# LEO_COTS_no_mult_tripler_rev1.net
KiCad netlist of a schematic drawn in Altium Designer
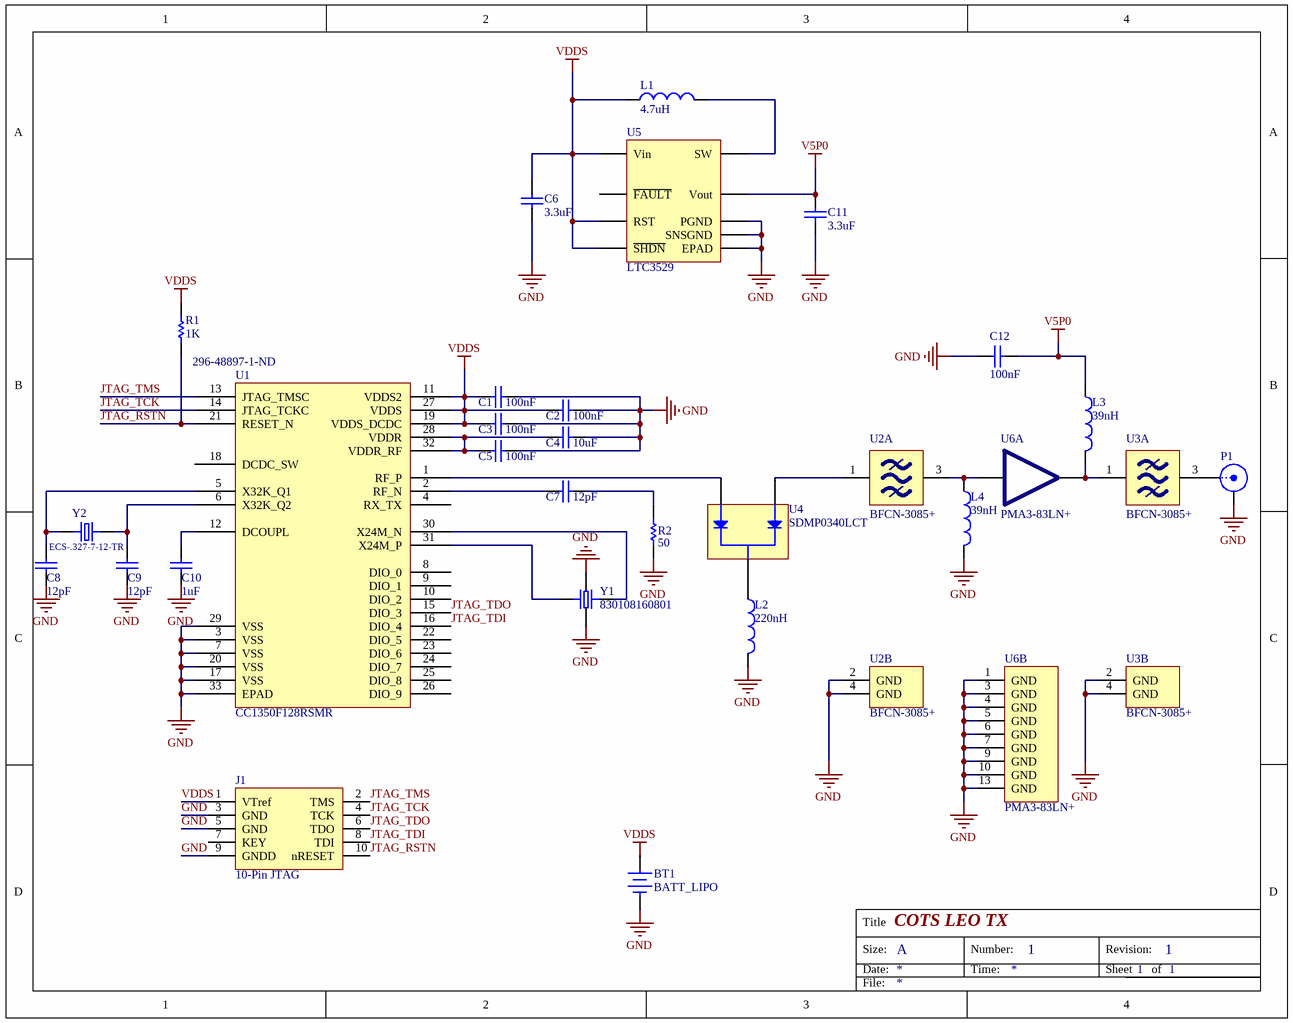
[diagram p0: LEO_COTS_no_mult_tripler_rev1.SchDoc]

(export (version "E")
  (design (tool "Eeschema 10.0.6"))
  (components
    (comp (ref "BT1")
      (value "BATT_LIPO")
      (footprint "LIPO_1cm_1cm")
      (libsource (lib "LEO_COTS_components") (part "BATT_LIPO"))
    )
    (comp (ref "C1")
      (value "100nF")
      (footprint "CAPC0603X04N")
      (description "CAP CER 100nF 0201")
      (fields (field (name "Comment") "CAP_0201"))
      (libsource (lib "LEO_COTS_components") (part "CAP_0201"))
    )
    (comp (ref "C2")
      (value "100nF")
      (footprint "CAPC0603X04N")
      (description "CAP CER 100nF 0201")
      (fields (field (name "Comment") "CAP_0201"))
      (libsource (lib "LEO_COTS_components") (part "CAP_0201"))
    )
    (comp (ref "C3")
      (value "100nF")
      (footprint "CAPC0603X04N")
      (description "CAP CER 100nF 0201")
      (fields (field (name "Comment") "CAP_0201"))
      (libsource (lib "LEO_COTS_components") (part "CAP_0201"))
    )
    (comp (ref "C4")
      (value "10uF")
      (footprint "CAPC1608X05N")
      (description "CAP CER 10uF 0603")
      (fields (field (name "Comment") "CAP_0603"))
      (libsource (lib "LEO_COTS_components") (part "CAP_0603"))
    )
    (comp (ref "C5")
      (value "100nF")
      (footprint "CAPC0603X04N")
      (description "CAP CER 100nF 0201")
      (fields (field (name "Comment") "CAP_0201"))
      (libsource (lib "LEO_COTS_components") (part "CAP_0201"))
    )
    (comp (ref "C6")
      (value "3.3uF")
      (footprint "CAPC1608X05N")
      (description "CAP CER 3.3uF 0603")
      (fields (field (name "Comment") "CAP_0603"))
      (libsource (lib "LEO_COTS_components") (part "CAP_0603"))
    )
    (comp (ref "C7")
      (value "12pF")
      (footprint "CAPC0603X04N")
      (description "CAP CER 12pF 0201")
      (fields (field (name "Comment") "CAP_0201"))
      (libsource (lib "LEO_COTS_components") (part "CAP_0201"))
    )
    (comp (ref "C8")
      (value "12pF")
      (footprint "CAPC0603X04N")
      (description "CAP CER 12pF 0201")
      (fields (field (name "Comment") "CAP_0201"))
      (libsource (lib "LEO_COTS_components") (part "CAP_0201"))
    )
    (comp (ref "C9")
      (value "12pF")
      (footprint "CAPC0603X04N")
      (description "CAP CER 12pF 0201")
      (fields (field (name "Comment") "CAP_0201"))
      (libsource (lib "LEO_COTS_components") (part "CAP_0201"))
    )
    (comp (ref "C10")
      (value "1uF")
      (footprint "CAPC0603X04N")
      (description "CAP CER 1uF 0201")
      (fields (field (name "Comment") "CAP_0201"))
      (libsource (lib "LEO_COTS_components") (part "CAP_0201"))
    )
    (comp (ref "C11")
      (value "3.3uF")
      (footprint "CAPC1608X05N")
      (description "CAP CER 3.3uF 0603")
      (fields (field (name "Comment") "CAP_0603"))
      (libsource (lib "LEO_COTS_components") (part "CAP_0603"))
    )
    (comp (ref "C12")
      (value "100nF")
      (footprint "CAPC0603X04N")
      (description "CAP CER 100nF 0201")
      (fields (field (name "Comment") "CAP_0201"))
      (libsource (lib "LEO_COTS_components") (part "CAP_0201"))
    )
    (comp (ref "J1")
      (value "10-Pin JTAG")
      (footprint "FTSH-105-01-F-DV-007-K")
      (description "10-pin JTAG")
      (libsource (lib "LEO_COTS_components") (part "CM10"))
    )
    (comp (ref "L1")
      (value "4.7uH")
      (footprint "C0805")
      (description "Inductor")
      (fields (field (name "PUBLISHER") "Altium Limited"))
      (libsource (lib "LEO_COTS_components") (part "Inductor"))
    )
    (comp (ref "L2")
      (value "220nH")
      (footprint "0402")
      (description "Inductor")
      (fields (field (name "PUBLISHER") "Altium Limited"))
      (libsource (lib "LEO_COTS_components") (part "Inductor"))
    )
    (comp (ref "L3")
      (value "39nH")
      (footprint "0402")
      (description "Inductor")
      (fields (field (name "PUBLISHER") "Altium Limited"))
      (libsource (lib "LEO_COTS_components") (part "Inductor"))
    )
    (comp (ref "L4")
      (value "39nH")
      (footprint "0402")
      (description "Inductor")
      (fields (field (name "PUBLISHER") "Altium Limited"))
      (libsource (lib "LEO_COTS_components") (part "Inductor"))
    )
    (comp (ref "P1")
      (value "1909763-1")
      (footprint "1909763-1")
      (description "CONN UMCC JACK STR 50OHM SMD")
      (libsource (lib "LEO_COTS_components") (part "1909763-1"))
    )
    (comp (ref "R1")
      (value "1K")
      (footprint "CAPC0603X04N")
      (description "RES 1K OHM 0201")
      (fields (field (name "Comment") "RES_0201") (field (name "PUBLISHER") "Altium Limited"))
      (libsource (lib "LEO_COTS_components") (part "Res Semi"))
    )
    (comp (ref "R2")
      (value "50")
      (footprint "CAPC0603X04N")
      (description "RES 50 OHM 0201")
      (fields (field (name "Comment") "RES_0201") (field (name "PUBLISHER") "Altium Limited"))
      (libsource (lib "LEO_COTS_components") (part "Res Semi"))
    )
    (comp (ref "U1")
      (value "CC1350F128RSMR")
      (footprint "QFN40P400X400X100-33N")
      (description "Ultra-Low-Power Dual-Band Wireless MCU")
      (fields (field (name "SUPPLIER PART NUMBER 1") "296-48897-1-ND"))
      (libsource (lib "LEO_COTS_components") (part "CC1350F128RSMR"))
    )
    (comp (ref "U2")
      (value "BFCN-3085+")
      (footprint "FV1206")
      (description "2800 to 3400 MHz Band-Pass Filter")
      (libsource (lib "LEO_COTS_components") (part "BFCN-3085+"))
    )
    (comp (ref "U3")
      (value "BFCN-3085+")
      (footprint "FV1206")
      (description "2800 to 3400 MHz Band-Pass Filter")
      (libsource (lib "LEO_COTS_components") (part "BFCN-3085+"))
    )
    (comp (ref "U4")
      (value "SDMP0340LCT")
      (footprint "SOT-523")
      (description "Dual Common Cathode Schottky")
      (libsource (lib "LEO_COTS_components") (part "SDMP0340LCT"))
    )
    (comp (ref "U5")
      (value "LTC3529")
      (footprint "8-DFN")
      (description "5V Boost Converter")
      (libsource (lib "LEO_COTS_components") (part "LTC3529"))
    )
    (comp (ref "U6")
      (value "PMA3-83LN+")
      (footprint "DQ1225")
      (description "Wideband LNA")
      (libsource (lib "LEO_COTS_components") (part "PMA3-83LN+"))
    )
    (comp (ref "Y1")
      (value "830108160801")
      (footprint "LFXTAL081608")
      (description "24 MHz crystal")
      (fields (field (name "MP") "ECS-.327-7-12-TR"))
      (libsource (lib "LEO_COTS_components") (part "830108160801"))
    )
    (comp (ref "Y2")
      (value "ECS-.327-7-12-TR")
      (footprint "XTAL_ECS-.327-7-12-TR")
      (description "32.768 kHz SMD Crystal")
      (libsource (lib "LEO_COTS_components") (part "ECS-.327-7-12-TR"))
    )
  )
  (nets
    (net (code "1") (name "/JTAG_RSTN") (class "Default")
      (node (ref "J1") (pin "10") (pinfunction "nRESET_10") (pintype "passive"))
      (node (ref "R1") (pin "1") (pinfunction "1_1") (pintype "passive"))
      (node (ref "U1") (pin "21") (pinfunction "RESET_N_21") (pintype "passive"))
    )
    (net (code "2") (name "/JTAG_TCK") (class "Default")
      (node (ref "J1") (pin "4") (pinfunction "TCK_4") (pintype "passive"))
      (node (ref "U1") (pin "14") (pinfunction "JTAG_TCKC_14") (pintype "passive"))
    )
    (net (code "3") (name "/JTAG_TDI") (class "Default")
      (node (ref "J1") (pin "8") (pinfunction "TDI_8") (pintype "passive"))
      (node (ref "U1") (pin "16") (pinfunction "DIO_4_16") (pintype "passive"))
    )
    (net (code "4") (name "/JTAG_TDO") (class "Default")
      (node (ref "J1") (pin "6") (pinfunction "TDO_6") (pintype "passive"))
      (node (ref "U1") (pin "15") (pinfunction "DIO_3_15") (pintype "passive"))
    )
    (net (code "5") (name "/JTAG_TMS") (class "Default")
      (node (ref "J1") (pin "2") (pinfunction "TMS_2") (pintype "passive"))
      (node (ref "U1") (pin "13") (pinfunction "JTAG_TMSC_13") (pintype "passive"))
    )
    (net (code "6") (name "GND") (class "Default")
      (node (ref "BT1") (pin "2") (pinfunction "-_2") (pintype "passive"))
      (node (ref "C1") (pin "1") (pinfunction "1_1") (pintype "passive"))
      (node (ref "C10") (pin "1") (pinfunction "1_1") (pintype "passive"))
      (node (ref "C11") (pin "1") (pinfunction "1_1") (pintype "passive"))
      (node (ref "C12") (pin "1") (pinfunction "1_1") (pintype "passive"))
      (node (ref "C2") (pin "1") (pinfunction "1_1") (pintype "passive"))
      (node (ref "C3") (pin "1") (pinfunction "1_1") (pintype "passive"))
      (node (ref "C4") (pin "2") (pinfunction "2_2") (pintype "passive"))
      (node (ref "C5") (pin "1") (pinfunction "1_1") (pintype "passive"))
      (node (ref "C6") (pin "1") (pinfunction "1_1") (pintype "passive"))
      (node (ref "C8") (pin "1") (pinfunction "1_1") (pintype "passive"))
      (node (ref "C9") (pin "1") (pinfunction "1_1") (pintype "passive"))
      (node (ref "J1") (pin "3") (pinfunction "GND_3") (pintype "passive"))
      (node (ref "J1") (pin "5") (pinfunction "GND_5") (pintype "passive"))
      (node (ref "J1") (pin "9") (pinfunction "GNDD_9") (pintype "passive"))
      (node (ref "L2") (pin "2") (pinfunction "2_2") (pintype "passive"))
      (node (ref "L4") (pin "2") (pinfunction "2_2") (pintype "passive"))
      (node (ref "P1") (pin "2") (pinfunction "Y_2") (pintype "passive"))
      (node (ref "R2") (pin "1") (pinfunction "1_1") (pintype "passive"))
      (node (ref "U1") (pin "17") (pinfunction "VSS_17") (pintype "passive"))
      (node (ref "U1") (pin "20") (pinfunction "VSS_20") (pintype "passive"))
      (node (ref "U1") (pin "29") (pinfunction "VSS_29") (pintype "passive"))
      (node (ref "U1") (pin "3") (pinfunction "VSS_3") (pintype "passive"))
      (node (ref "U1") (pin "33") (pinfunction "EPAD_33") (pintype "passive"))
      (node (ref "U1") (pin "7") (pinfunction "VSS_7") (pintype "passive"))
      (node (ref "U2") (pin "2") (pinfunction "GND_2") (pintype "tri_state"))
      (node (ref "U2") (pin "4") (pinfunction "GND_4") (pintype "tri_state"))
      (node (ref "U3") (pin "2") (pinfunction "GND_2") (pintype "tri_state"))
      (node (ref "U3") (pin "4") (pinfunction "GND_4") (pintype "tri_state"))
      (node (ref "U5") (pin "4") (pinfunction "PGND_4") (pintype "passive"))
      (node (ref "U5") (pin "6") (pinfunction "SNSGND_6") (pintype "passive"))
      (node (ref "U5") (pin "9") (pinfunction "EPAD_9") (pintype "passive"))
      (node (ref "U6") (pin "1") (pinfunction "GND_1") (pintype "tri_state"))
      (node (ref "U6") (pin "10") (pinfunction "GND_10") (pintype "tri_state"))
      (node (ref "U6") (pin "13") (pinfunction "GND_13") (pintype "tri_state"))
      (node (ref "U6") (pin "3") (pinfunction "GND_3") (pintype "tri_state"))
      (node (ref "U6") (pin "4") (pinfunction "GND_4") (pintype "tri_state"))
      (node (ref "U6") (pin "5") (pinfunction "GND_5") (pintype "tri_state"))
      (node (ref "U6") (pin "6") (pinfunction "GND_6") (pintype "tri_state"))
      (node (ref "U6") (pin "7") (pinfunction "GND_7") (pintype "tri_state"))
      (node (ref "U6") (pin "9") (pinfunction "GND_9") (pintype "tri_state"))
      (node (ref "Y1") (pin "2") (pinfunction "2_2") (pintype "passive"))
      (node (ref "Y1") (pin "4") (pinfunction "4_4") (pintype "passive"))
    )
    (net (code "7") (name "Net-(C7-Pad1)") (class "Default")
      (node (ref "C7") (pin "1") (pinfunction "1_1") (pintype "passive"))
      (node (ref "R2") (pin "2") (pinfunction "2_2") (pintype "passive"))
    )
    (net (code "8") (name "Net-(L2-Pad1)") (class "Default")
      (node (ref "L2") (pin "1") (pinfunction "1_1") (pintype "passive"))
      (node (ref "U4") (pin "3") (pinfunction "3_3") (pintype "passive"))
    )
    (net (code "9") (name "Net-(P1-X)") (class "Default")
      (node (ref "P1") (pin "1") (pinfunction "X_1") (pintype "passive"))
      (node (ref "U3") (pin "3") (pinfunction "OUT_3") (pintype "tri_state"))
    )
    (net (code "10") (name "Net-(U1-DCOUPL)") (class "Default")
      (node (ref "C10") (pin "2") (pinfunction "2_2") (pintype "passive"))
      (node (ref "U1") (pin "12") (pinfunction "DCOUPL_12") (pintype "passive"))
    )
    (net (code "11") (name "Net-(U1-RF_N)") (class "Default")
      (node (ref "C7") (pin "2") (pinfunction "2_2") (pintype "passive"))
      (node (ref "U1") (pin "2") (pinfunction "RF_N_2") (pintype "passive"))
    )
    (net (code "12") (name "Net-(U1-RF_P)") (class "Default")
      (node (ref "U1") (pin "1") (pinfunction "RF_P_1") (pintype "passive"))
      (node (ref "U4") (pin "1") (pinfunction "1_1") (pintype "passive"))
    )
    (net (code "13") (name "Net-(U1-VDDR)") (class "Default")
      (node (ref "C4") (pin "1") (pinfunction "1_1") (pintype "passive"))
      (node (ref "C5") (pin "2") (pinfunction "2_2") (pintype "passive"))
      (node (ref "U1") (pin "28") (pinfunction "VDDR_28") (pintype "passive"))
      (node (ref "U1") (pin "32") (pinfunction "VDDR_RF_32") (pintype "passive"))
    )
    (net (code "14") (name "Net-(U1-X24M_N)") (class "Default")
      (node (ref "U1") (pin "30") (pinfunction "X24M_N_30") (pintype "passive"))
      (node (ref "Y1") (pin "3") (pinfunction "3_3") (pintype "passive"))
    )
    (net (code "15") (name "Net-(U1-X24M_P)") (class "Default")
      (node (ref "U1") (pin "31") (pinfunction "X24M_P_31") (pintype "passive"))
      (node (ref "Y1") (pin "1") (pinfunction "1_1") (pintype "passive"))
    )
    (net (code "16") (name "Net-(U1-X32K_Q1)") (class "Default")
      (node (ref "C8") (pin "2") (pinfunction "2_2") (pintype "passive"))
      (node (ref "U1") (pin "5") (pinfunction "X32K_Q1_5") (pintype "passive"))
      (node (ref "Y2") (pin "1") (pinfunction "1_1") (pintype "passive"))
    )
    (net (code "17") (name "Net-(U1-X32K_Q2)") (class "Default")
      (node (ref "C9") (pin "2") (pinfunction "2_2") (pintype "passive"))
      (node (ref "U1") (pin "6") (pinfunction "X32K_Q2_6") (pintype "passive"))
      (node (ref "Y2") (pin "2") (pinfunction "2_2") (pintype "passive"))
    )
    (net (code "18") (name "Net-(U2A-IN)") (class "Default")
      (node (ref "U2") (pin "1") (pinfunction "IN_1") (pintype "tri_state"))
      (node (ref "U4") (pin "2") (pinfunction "2_2") (pintype "passive"))
    )
    (net (code "19") (name "Net-(U2A-OUT)") (class "Default")
      (node (ref "L4") (pin "1") (pinfunction "1_1") (pintype "passive"))
      (node (ref "U2") (pin "3") (pinfunction "OUT_3") (pintype "tri_state"))
      (node (ref "U6") (pin "2") (pinfunction "IN_2") (pintype "tri_state"))
    )
    (net (code "20") (name "Net-(U3A-IN)") (class "Default")
      (node (ref "L3") (pin "2") (pinfunction "2_2") (pintype "passive"))
      (node (ref "U3") (pin "1") (pinfunction "IN_1") (pintype "tri_state"))
      (node (ref "U6") (pin "8") (pinfunction "OUT_8") (pintype "tri_state"))
    )
    (net (code "21") (name "Net-(U5-SW)") (class "Default")
      (node (ref "L1") (pin "2") (pinfunction "2_2") (pintype "passive"))
      (node (ref "U5") (pin "2") (pinfunction "SW_2") (pintype "passive"))
    )
    (net (code "22") (name "V5P0") (class "Default")
      (node (ref "C11") (pin "2") (pinfunction "2_2") (pintype "passive"))
      (node (ref "C12") (pin "2") (pinfunction "2_2") (pintype "passive"))
      (node (ref "L3") (pin "1") (pinfunction "1_1") (pintype "passive"))
      (node (ref "U5") (pin "1") (pinfunction "Vout_1") (pintype "passive"))
    )
    (net (code "23") (name "VDDS") (class "Default")
      (node (ref "BT1") (pin "1") (pinfunction "+_1") (pintype "passive"))
      (node (ref "C1") (pin "2") (pinfunction "2_2") (pintype "passive"))
      (node (ref "C2") (pin "2") (pinfunction "2_2") (pintype "passive"))
      (node (ref "C3") (pin "2") (pinfunction "2_2") (pintype "passive"))
      (node (ref "C6") (pin "2") (pinfunction "2_2") (pintype "passive"))
      (node (ref "J1") (pin "1") (pinfunction "VTref_1") (pintype "passive"))
      (node (ref "L1") (pin "1") (pinfunction "1_1") (pintype "passive"))
      (node (ref "R1") (pin "2") (pinfunction "2_2") (pintype "passive"))
      (node (ref "U1") (pin "11") (pinfunction "VDDS2_11") (pintype "passive"))
      (node (ref "U1") (pin "19") (pinfunction "VDDS_DCDC_19") (pintype "passive"))
      (node (ref "U1") (pin "27") (pinfunction "VDDS_27") (pintype "passive"))
      (node (ref "U5") (pin "3") (pinfunction "~{SHDN}_3") (pintype "passive"))
      (node (ref "U5") (pin "7") (pinfunction "RST_7") (pintype "passive"))
      (node (ref "U5") (pin "8") (pinfunction "Vin_8") (pintype "passive"))
    )
    (net (code "24") (name "unconnected-(J1-KEY-Pad7)") (class "Default")
      (node (ref "J1") (pin "7") (pinfunction "KEY_7") (pintype "passive"))
    )
    (net (code "25") (name "unconnected-(U1-DCDC_SW-Pad18)") (class "Default")
      (node (ref "U1") (pin "18") (pinfunction "DCDC_SW_18") (pintype "passive"))
    )
    (net (code "26") (name "unconnected-(U1-DIO_0-Pad8)") (class "Default")
      (node (ref "U1") (pin "8") (pinfunction "DIO_0_8") (pintype "passive"))
    )
    (net (code "27") (name "unconnected-(U1-DIO_1-Pad9)") (class "Default")
      (node (ref "U1") (pin "9") (pinfunction "DIO_1_9") (pintype "passive"))
    )
    (net (code "28") (name "unconnected-(U1-DIO_2-Pad10)") (class "Default")
      (node (ref "U1") (pin "10") (pinfunction "DIO_2_10") (pintype "passive"))
    )
    (net (code "29") (name "unconnected-(U1-DIO_5-Pad22)") (class "Default")
      (node (ref "U1") (pin "22") (pinfunction "DIO_5_22") (pintype "passive"))
    )
    (net (code "30") (name "unconnected-(U1-DIO_6-Pad23)") (class "Default")
      (node (ref "U1") (pin "23") (pinfunction "DIO_6_23") (pintype "passive"))
    )
    (net (code "31") (name "unconnected-(U1-DIO_7-Pad24)") (class "Default")
      (node (ref "U1") (pin "24") (pinfunction "DIO_7_24") (pintype "passive"))
    )
    (net (code "32") (name "unconnected-(U1-DIO_8-Pad25)") (class "Default")
      (node (ref "U1") (pin "25") (pinfunction "DIO_8_25") (pintype "passive"))
    )
    (net (code "33") (name "unconnected-(U1-DIO_9-Pad26)") (class "Default")
      (node (ref "U1") (pin "26") (pinfunction "DIO_9_26") (pintype "passive"))
    )
    (net (code "34") (name "unconnected-(U1-RX_TX-Pad4)") (class "Default")
      (node (ref "U1") (pin "4") (pinfunction "RX_TX_4") (pintype "passive"))
    )
    (net (code "35") (name "unconnected-(U5-~{FAULT}-Pad5)") (class "Default")
      (node (ref "U5") (pin "5") (pinfunction "~{FAULT}_5") (pintype "passive"))
    )
  )
)
